# Quad-Load-Cell-Amplifier-to-RS-485-Conv-.net
KiCad netlist of a schematic drawn in EAGLE
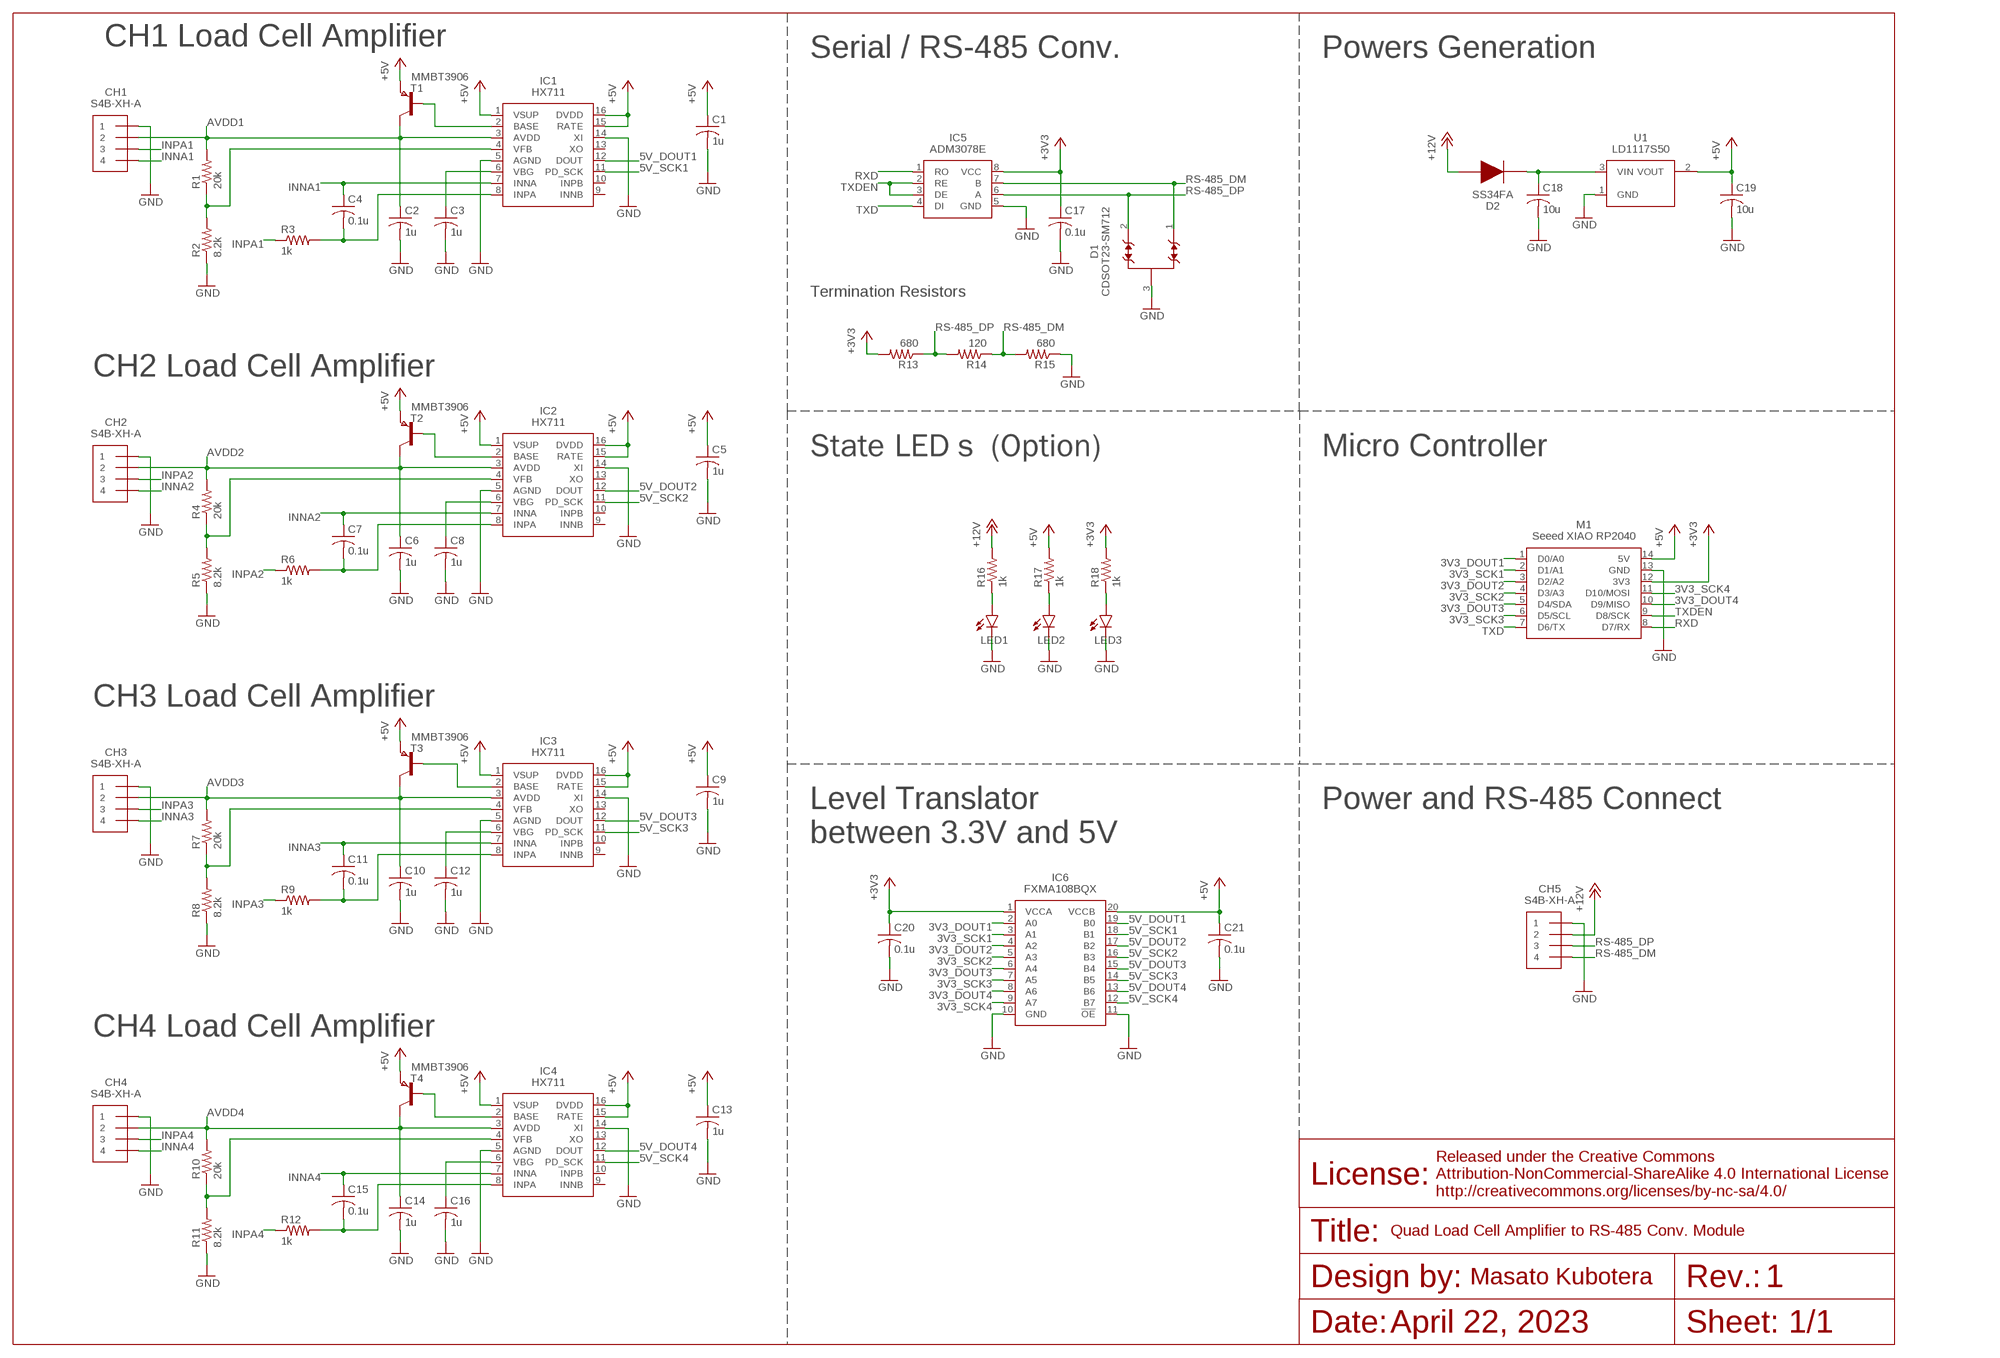
[diagram p0: schematic, sheet 1]

(export (version "E")
  (design (tool "Eeschema 10.0.6"))
  (components
    (comp (ref "C1")
      (value "1u")
      (footprint "eagle-import:C0603")
      (libsource (lib "eagle-import") (part "C-USC0603"))
    )
    (comp (ref "C2")
      (value "1u")
      (footprint "eagle-import:C0603")
      (libsource (lib "eagle-import") (part "C-USC0603"))
    )
    (comp (ref "C3")
      (value "1u")
      (footprint "eagle-import:C0603")
      (libsource (lib "eagle-import") (part "C-USC0603"))
    )
    (comp (ref "C4")
      (value "0.1u")
      (footprint "eagle-import:C0603")
      (libsource (lib "eagle-import") (part "C-USC0603"))
    )
    (comp (ref "C5")
      (value "1u")
      (footprint "eagle-import:C0603")
      (libsource (lib "eagle-import") (part "C-USC0603"))
    )
    (comp (ref "C6")
      (value "1u")
      (footprint "eagle-import:C0603")
      (libsource (lib "eagle-import") (part "C-USC0603"))
    )
    (comp (ref "C7")
      (value "0.1u")
      (footprint "eagle-import:C0603")
      (libsource (lib "eagle-import") (part "C-USC0603"))
    )
    (comp (ref "C8")
      (value "1u")
      (footprint "eagle-import:C0603")
      (libsource (lib "eagle-import") (part "C-USC0603"))
    )
    (comp (ref "C9")
      (value "1u")
      (footprint "eagle-import:C0603")
      (libsource (lib "eagle-import") (part "C-USC0603"))
    )
    (comp (ref "C10")
      (value "1u")
      (footprint "eagle-import:C0603")
      (libsource (lib "eagle-import") (part "C-USC0603"))
    )
    (comp (ref "C11")
      (value "0.1u")
      (footprint "eagle-import:C0603")
      (libsource (lib "eagle-import") (part "C-USC0603"))
    )
    (comp (ref "C12")
      (value "1u")
      (footprint "eagle-import:C0603")
      (libsource (lib "eagle-import") (part "C-USC0603"))
    )
    (comp (ref "C13")
      (value "1u")
      (footprint "eagle-import:C0603")
      (libsource (lib "eagle-import") (part "C-USC0603"))
    )
    (comp (ref "C14")
      (value "1u")
      (footprint "eagle-import:C0603")
      (libsource (lib "eagle-import") (part "C-USC0603"))
    )
    (comp (ref "C15")
      (value "0.1u")
      (footprint "eagle-import:C0603")
      (libsource (lib "eagle-import") (part "C-USC0603"))
    )
    (comp (ref "C16")
      (value "1u")
      (footprint "eagle-import:C0603")
      (libsource (lib "eagle-import") (part "C-USC0603"))
    )
    (comp (ref "C17")
      (value "0.1u")
      (footprint "eagle-import:C0603")
      (libsource (lib "eagle-import") (part "C-USC0603"))
    )
    (comp (ref "C18")
      (value "10u")
      (footprint "eagle-import:C0603")
      (libsource (lib "eagle-import") (part "C-USC0603"))
    )
    (comp (ref "C19")
      (value "10u")
      (footprint "eagle-import:C0603")
      (libsource (lib "eagle-import") (part "C-USC0603"))
    )
    (comp (ref "C20")
      (value "0.1u")
      (footprint "eagle-import:C0603")
      (libsource (lib "eagle-import") (part "C-USC0603"))
    )
    (comp (ref "C21")
      (value "0.1u")
      (footprint "eagle-import:C0603")
      (libsource (lib "eagle-import") (part "C-USC0603"))
    )
    (comp (ref "CH1")
      (value "S4B-XH-A")
      (footprint "eagle-import:S4B-XH-A")
      (libsource (lib "eagle-import") (part "S4B-XH-A"))
    )
    (comp (ref "CH2")
      (value "S4B-XH-A")
      (footprint "eagle-import:S4B-XH-A")
      (libsource (lib "eagle-import") (part "S4B-XH-A"))
    )
    (comp (ref "CH3")
      (value "S4B-XH-A")
      (footprint "eagle-import:S4B-XH-A")
      (libsource (lib "eagle-import") (part "S4B-XH-A"))
    )
    (comp (ref "CH4")
      (value "S4B-XH-A")
      (footprint "eagle-import:S4B-XH-A")
      (libsource (lib "eagle-import") (part "S4B-XH-A"))
    )
    (comp (ref "CH5")
      (value "S4B-XH-A")
      (footprint "eagle-import:S4B-XH-A")
      (libsource (lib "eagle-import") (part "S4B-XH-A"))
    )
    (comp (ref "D1")
      (value "CDSOT23-SM712")
      (footprint "eagle-import:SOT-23-3")
      (libsource (lib "eagle-import") (part "CDSOT23-SM712"))
    )
    (comp (ref "D2")
      (value "SS34FA")
      (footprint "eagle-import:SS34FA")
      (libsource (lib "eagle-import") (part "SS34FA"))
    )
    (comp (ref "IC1")
      (value "HX711")
      (footprint "eagle-import:HX711")
      (libsource (lib "eagle-import") (part "HX711"))
    )
    (comp (ref "IC2")
      (value "HX711")
      (footprint "eagle-import:HX711")
      (libsource (lib "eagle-import") (part "HX711"))
    )
    (comp (ref "IC3")
      (value "HX711")
      (footprint "eagle-import:HX711")
      (libsource (lib "eagle-import") (part "HX711"))
    )
    (comp (ref "IC4")
      (value "HX711")
      (footprint "eagle-import:HX711")
      (libsource (lib "eagle-import") (part "HX711"))
    )
    (comp (ref "IC5")
      (value "ADM3078E")
      (footprint "eagle-import:ADM3078E")
      (libsource (lib "eagle-import") (part "ADM3078E"))
    )
    (comp (ref "IC6")
      (value "FXMA108BQX")
      (footprint "eagle-import:QFN-20")
      (libsource (lib "eagle-import") (part "FXMA108BQX"))
    )
    (comp (ref "LED1")
      (value "LEDSML0603")
      (footprint "eagle-import:SML0603")
      (libsource (lib "eagle-import") (part "LEDSML0603"))
    )
    (comp (ref "LED2")
      (value "LEDSML0603")
      (footprint "eagle-import:SML0603")
      (libsource (lib "eagle-import") (part "LEDSML0603"))
    )
    (comp (ref "LED3")
      (value "LEDSML0603")
      (footprint "eagle-import:SML0603")
      (libsource (lib "eagle-import") (part "LEDSML0603"))
    )
    (comp (ref "M1")
      (value "SEEED_XIAO_RP2040_HOLE")
      (footprint "eagle-import:SEEED_XIAO_HOLE")
      (libsource (lib "eagle-import") (part "SEEED_XIAO_RP2040_HOLE"))
    )
    (comp (ref "R1")
      (value "20k")
      (footprint "eagle-import:R0603")
      (libsource (lib "eagle-import") (part "R-US_R0603"))
    )
    (comp (ref "R2")
      (value "8.2k")
      (footprint "eagle-import:R0603")
      (libsource (lib "eagle-import") (part "R-US_R0603"))
    )
    (comp (ref "R3")
      (value "1k")
      (footprint "eagle-import:R0603")
      (libsource (lib "eagle-import") (part "R-US_R0603"))
    )
    (comp (ref "R4")
      (value "20k")
      (footprint "eagle-import:R0603")
      (libsource (lib "eagle-import") (part "R-US_R0603"))
    )
    (comp (ref "R5")
      (value "8.2k")
      (footprint "eagle-import:R0603")
      (libsource (lib "eagle-import") (part "R-US_R0603"))
    )
    (comp (ref "R6")
      (value "1k")
      (footprint "eagle-import:R0603")
      (libsource (lib "eagle-import") (part "R-US_R0603"))
    )
    (comp (ref "R7")
      (value "20k")
      (footprint "eagle-import:R0603")
      (libsource (lib "eagle-import") (part "R-US_R0603"))
    )
    (comp (ref "R8")
      (value "8.2k")
      (footprint "eagle-import:R0603")
      (libsource (lib "eagle-import") (part "R-US_R0603"))
    )
    (comp (ref "R9")
      (value "1k")
      (footprint "eagle-import:R0603")
      (libsource (lib "eagle-import") (part "R-US_R0603"))
    )
    (comp (ref "R10")
      (value "20k")
      (footprint "eagle-import:R0603")
      (libsource (lib "eagle-import") (part "R-US_R0603"))
    )
    (comp (ref "R11")
      (value "8.2k")
      (footprint "eagle-import:R0603")
      (libsource (lib "eagle-import") (part "R-US_R0603"))
    )
    (comp (ref "R12")
      (value "1k")
      (footprint "eagle-import:R0603")
      (libsource (lib "eagle-import") (part "R-US_R0603"))
    )
    (comp (ref "R13")
      (value "680")
      (footprint "eagle-import:R0603")
      (libsource (lib "eagle-import") (part "R-US_R0603"))
    )
    (comp (ref "R14")
      (value "120")
      (footprint "eagle-import:R0603")
      (libsource (lib "eagle-import") (part "R-US_R0603"))
    )
    (comp (ref "R15")
      (value "680")
      (footprint "eagle-import:R0603")
      (libsource (lib "eagle-import") (part "R-US_R0603"))
    )
    (comp (ref "R16")
      (value "1k")
      (footprint "eagle-import:R0603")
      (libsource (lib "eagle-import") (part "R-US_R0603"))
    )
    (comp (ref "R17")
      (value "1k")
      (footprint "eagle-import:R0603")
      (libsource (lib "eagle-import") (part "R-US_R0603"))
    )
    (comp (ref "R18")
      (value "1k")
      (footprint "eagle-import:R0603")
      (libsource (lib "eagle-import") (part "R-US_R0603"))
    )
    (comp (ref "T1")
      (value "MMBT3906")
      (footprint "eagle-import:SOT-23")
      (fields (field (name "MPN") "DSS20200L-7"))
      (libsource (lib "eagle-import") (part "PNPSOT23"))
    )
    (comp (ref "T2")
      (value "MMBT3906")
      (footprint "eagle-import:SOT-23")
      (fields (field (name "MPN") "DSS20200L-7"))
      (libsource (lib "eagle-import") (part "PNPSOT23"))
    )
    (comp (ref "T3")
      (value "MMBT3906")
      (footprint "eagle-import:SOT-23")
      (fields (field (name "MPN") "DSS20200L-7"))
      (libsource (lib "eagle-import") (part "PNPSOT23"))
    )
    (comp (ref "T4")
      (value "MMBT3906")
      (footprint "eagle-import:SOT-23")
      (fields (field (name "MPN") "DSS20200L-7"))
      (libsource (lib "eagle-import") (part "PNPSOT23"))
    )
    (comp (ref "U1")
      (value "LD1117S50")
      (footprint "eagle-import:SOT-223")
      (libsource (lib "eagle-import") (part "LD1117S50"))
    )
  )
  (nets
    (net (code "1") (name "+3V3") (class "Default")
      (node (ref "C17") (pin "1") (pinfunction "1_1") (pintype "passive"))
      (node (ref "C20") (pin "1") (pinfunction "1_1") (pintype "passive"))
      (node (ref "IC5") (pin "8") (pinfunction "VCC_8") (pintype "bidirectional"))
      (node (ref "IC6") (pin "1") (pinfunction "VCCA_1") (pintype "bidirectional"))
      (node (ref "M1") (pin "12") (pinfunction "3V3_12") (pintype "bidirectional"))
      (node (ref "R13") (pin "2") (pinfunction "2_2") (pintype "passive"))
      (node (ref "R18") (pin "2") (pinfunction "2_2") (pintype "passive"))
    )
    (net (code "2") (name "+5V") (class "Default")
      (node (ref "C1") (pin "1") (pinfunction "1_1") (pintype "passive"))
      (node (ref "C13") (pin "1") (pinfunction "1_1") (pintype "passive"))
      (node (ref "C19") (pin "1") (pinfunction "1_1") (pintype "passive"))
      (node (ref "C21") (pin "1") (pinfunction "1_1") (pintype "passive"))
      (node (ref "C5") (pin "1") (pinfunction "1_1") (pintype "passive"))
      (node (ref "C9") (pin "1") (pinfunction "1_1") (pintype "passive"))
      (node (ref "IC1") (pin "1") (pinfunction "VSUP_1") (pintype "bidirectional"))
      (node (ref "IC1") (pin "15") (pinfunction "RATE_15") (pintype "bidirectional"))
      (node (ref "IC1") (pin "16") (pinfunction "DVDD_16") (pintype "bidirectional"))
      (node (ref "IC2") (pin "1") (pinfunction "VSUP_1") (pintype "bidirectional"))
      (node (ref "IC2") (pin "15") (pinfunction "RATE_15") (pintype "bidirectional"))
      (node (ref "IC2") (pin "16") (pinfunction "DVDD_16") (pintype "bidirectional"))
      (node (ref "IC3") (pin "1") (pinfunction "VSUP_1") (pintype "bidirectional"))
      (node (ref "IC3") (pin "15") (pinfunction "RATE_15") (pintype "bidirectional"))
      (node (ref "IC3") (pin "16") (pinfunction "DVDD_16") (pintype "bidirectional"))
      (node (ref "IC4") (pin "1") (pinfunction "VSUP_1") (pintype "bidirectional"))
      (node (ref "IC4") (pin "15") (pinfunction "RATE_15") (pintype "bidirectional"))
      (node (ref "IC4") (pin "16") (pinfunction "DVDD_16") (pintype "bidirectional"))
      (node (ref "IC6") (pin "20") (pinfunction "VCCB_20") (pintype "bidirectional"))
      (node (ref "M1") (pin "14") (pinfunction "5V_14") (pintype "bidirectional"))
      (node (ref "R17") (pin "2") (pinfunction "2_2") (pintype "passive"))
      (node (ref "T1") (pin "2") (pinfunction "E_2") (pintype "passive"))
      (node (ref "T2") (pin "2") (pinfunction "E_2") (pintype "passive"))
      (node (ref "T3") (pin "2") (pinfunction "E_2") (pintype "passive"))
      (node (ref "T4") (pin "2") (pinfunction "E_2") (pintype "passive"))
      (node (ref "U1") (pin "2") (pinfunction "VOUT_2") (pintype "bidirectional"))
    )
    (net (code "3") (name "+12V") (class "Default")
      (node (ref "CH5") (pin "2") (pinfunction "2_2") (pintype "bidirectional"))
      (node (ref "D2") (pin "2") (pinfunction "2_2") (pintype "bidirectional"))
      (node (ref "R16") (pin "2") (pinfunction "2_2") (pintype "passive"))
    )
    (net (code "4") (name "/3V3_DOUT1") (class "Default")
      (node (ref "IC6") (pin "2") (pinfunction "A0_2") (pintype "bidirectional"))
      (node (ref "M1") (pin "1") (pinfunction "D0/A0_1") (pintype "bidirectional"))
    )
    (net (code "5") (name "/3V3_DOUT2") (class "Default")
      (node (ref "IC6") (pin "4") (pinfunction "A2_4") (pintype "bidirectional"))
      (node (ref "M1") (pin "3") (pinfunction "D2/A2_3") (pintype "bidirectional"))
    )
    (net (code "6") (name "/3V3_DOUT3") (class "Default")
      (node (ref "IC6") (pin "6") (pinfunction "A4_6") (pintype "bidirectional"))
      (node (ref "M1") (pin "5") (pinfunction "D4/SDA_5") (pintype "bidirectional"))
    )
    (net (code "7") (name "/3V3_DOUT4") (class "Default")
      (node (ref "IC6") (pin "8") (pinfunction "A6_8") (pintype "bidirectional"))
      (node (ref "M1") (pin "10") (pinfunction "D9/MISO_10") (pintype "bidirectional"))
    )
    (net (code "8") (name "/3V3_SCK1") (class "Default")
      (node (ref "IC6") (pin "3") (pinfunction "A1_3") (pintype "bidirectional"))
      (node (ref "M1") (pin "2") (pinfunction "D1/A1_2") (pintype "bidirectional"))
    )
    (net (code "9") (name "/3V3_SCK2") (class "Default")
      (node (ref "IC6") (pin "5") (pinfunction "A3_5") (pintype "bidirectional"))
      (node (ref "M1") (pin "4") (pinfunction "D3/A3_4") (pintype "bidirectional"))
    )
    (net (code "10") (name "/3V3_SCK3") (class "Default")
      (node (ref "IC6") (pin "7") (pinfunction "A5_7") (pintype "bidirectional"))
      (node (ref "M1") (pin "6") (pinfunction "D5/SCL_6") (pintype "bidirectional"))
    )
    (net (code "11") (name "/3V3_SCK4") (class "Default")
      (node (ref "IC6") (pin "9") (pinfunction "A7_9") (pintype "bidirectional"))
      (node (ref "M1") (pin "11") (pinfunction "D10/MOSI_11") (pintype "bidirectional"))
    )
    (net (code "12") (name "/5V_DOUT1") (class "Default")
      (node (ref "IC1") (pin "12") (pinfunction "DOUT_12") (pintype "bidirectional"))
      (node (ref "IC6") (pin "19") (pinfunction "B0_19") (pintype "bidirectional"))
    )
    (net (code "13") (name "/5V_DOUT2") (class "Default")
      (node (ref "IC2") (pin "12") (pinfunction "DOUT_12") (pintype "bidirectional"))
      (node (ref "IC6") (pin "17") (pinfunction "B2_17") (pintype "bidirectional"))
    )
    (net (code "14") (name "/5V_DOUT3") (class "Default")
      (node (ref "IC3") (pin "12") (pinfunction "DOUT_12") (pintype "bidirectional"))
      (node (ref "IC6") (pin "15") (pinfunction "B4_15") (pintype "bidirectional"))
    )
    (net (code "15") (name "/5V_DOUT4") (class "Default")
      (node (ref "IC4") (pin "12") (pinfunction "DOUT_12") (pintype "bidirectional"))
      (node (ref "IC6") (pin "13") (pinfunction "B6_13") (pintype "bidirectional"))
    )
    (net (code "16") (name "/5V_SCK1") (class "Default")
      (node (ref "IC1") (pin "11") (pinfunction "PD_SCK_11") (pintype "bidirectional"))
      (node (ref "IC6") (pin "18") (pinfunction "B1_18") (pintype "bidirectional"))
    )
    (net (code "17") (name "/5V_SCK2") (class "Default")
      (node (ref "IC2") (pin "11") (pinfunction "PD_SCK_11") (pintype "bidirectional"))
      (node (ref "IC6") (pin "16") (pinfunction "B3_16") (pintype "bidirectional"))
    )
    (net (code "18") (name "/5V_SCK3") (class "Default")
      (node (ref "IC3") (pin "11") (pinfunction "PD_SCK_11") (pintype "bidirectional"))
      (node (ref "IC6") (pin "14") (pinfunction "B5_14") (pintype "bidirectional"))
    )
    (net (code "19") (name "/5V_SCK4") (class "Default")
      (node (ref "IC4") (pin "11") (pinfunction "PD_SCK_11") (pintype "bidirectional"))
      (node (ref "IC6") (pin "12") (pinfunction "B7_12") (pintype "bidirectional"))
    )
    (net (code "20") (name "/AVDD1") (class "Default")
      (node (ref "C2") (pin "1") (pinfunction "1_1") (pintype "passive"))
      (node (ref "CH1") (pin "2") (pinfunction "2_2") (pintype "bidirectional"))
      (node (ref "IC1") (pin "3") (pinfunction "AVDD_3") (pintype "bidirectional"))
      (node (ref "R1") (pin "2") (pinfunction "2_2") (pintype "passive"))
      (node (ref "T1") (pin "1") (pinfunction "C_1") (pintype "passive"))
    )
    (net (code "21") (name "/AVDD2") (class "Default")
      (node (ref "C6") (pin "1") (pinfunction "1_1") (pintype "passive"))
      (node (ref "CH2") (pin "2") (pinfunction "2_2") (pintype "bidirectional"))
      (node (ref "IC2") (pin "3") (pinfunction "AVDD_3") (pintype "bidirectional"))
      (node (ref "R4") (pin "2") (pinfunction "2_2") (pintype "passive"))
      (node (ref "T2") (pin "1") (pinfunction "C_1") (pintype "passive"))
    )
    (net (code "22") (name "/AVDD3") (class "Default")
      (node (ref "C10") (pin "1") (pinfunction "1_1") (pintype "passive"))
      (node (ref "CH3") (pin "2") (pinfunction "2_2") (pintype "bidirectional"))
      (node (ref "IC3") (pin "3") (pinfunction "AVDD_3") (pintype "bidirectional"))
      (node (ref "R7") (pin "2") (pinfunction "2_2") (pintype "passive"))
      (node (ref "T3") (pin "1") (pinfunction "C_1") (pintype "passive"))
    )
    (net (code "23") (name "/AVDD4") (class "Default")
      (node (ref "C14") (pin "1") (pinfunction "1_1") (pintype "passive"))
      (node (ref "CH4") (pin "2") (pinfunction "2_2") (pintype "bidirectional"))
      (node (ref "IC4") (pin "3") (pinfunction "AVDD_3") (pintype "bidirectional"))
      (node (ref "R10") (pin "2") (pinfunction "2_2") (pintype "passive"))
      (node (ref "T4") (pin "1") (pinfunction "C_1") (pintype "passive"))
    )
    (net (code "24") (name "/INNA1") (class "Default")
      (node (ref "C4") (pin "1") (pinfunction "1_1") (pintype "passive"))
      (node (ref "CH1") (pin "4") (pinfunction "4_4") (pintype "bidirectional"))
      (node (ref "IC1") (pin "7") (pinfunction "INNA_7") (pintype "bidirectional"))
    )
    (net (code "25") (name "/INNA2") (class "Default")
      (node (ref "C7") (pin "1") (pinfunction "1_1") (pintype "passive"))
      (node (ref "CH2") (pin "4") (pinfunction "4_4") (pintype "bidirectional"))
      (node (ref "IC2") (pin "7") (pinfunction "INNA_7") (pintype "bidirectional"))
    )
    (net (code "26") (name "/INNA3") (class "Default")
      (node (ref "C11") (pin "1") (pinfunction "1_1") (pintype "passive"))
      (node (ref "CH3") (pin "4") (pinfunction "4_4") (pintype "bidirectional"))
      (node (ref "IC3") (pin "7") (pinfunction "INNA_7") (pintype "bidirectional"))
    )
    (net (code "27") (name "/INNA4") (class "Default")
      (node (ref "C15") (pin "1") (pinfunction "1_1") (pintype "passive"))
      (node (ref "CH4") (pin "4") (pinfunction "4_4") (pintype "bidirectional"))
      (node (ref "IC4") (pin "7") (pinfunction "INNA_7") (pintype "bidirectional"))
    )
    (net (code "28") (name "/INPA1") (class "Default")
      (node (ref "CH1") (pin "3") (pinfunction "3_3") (pintype "bidirectional"))
      (node (ref "R3") (pin "1") (pinfunction "1_1") (pintype "passive"))
    )
    (net (code "29") (name "/INPA2") (class "Default")
      (node (ref "CH2") (pin "3") (pinfunction "3_3") (pintype "bidirectional"))
      (node (ref "R6") (pin "1") (pinfunction "1_1") (pintype "passive"))
    )
    (net (code "30") (name "/INPA3") (class "Default")
      (node (ref "CH3") (pin "3") (pinfunction "3_3") (pintype "bidirectional"))
      (node (ref "R9") (pin "1") (pinfunction "1_1") (pintype "passive"))
    )
    (net (code "31") (name "/INPA4") (class "Default")
      (node (ref "CH4") (pin "3") (pinfunction "3_3") (pintype "bidirectional"))
      (node (ref "R12") (pin "1") (pinfunction "1_1") (pintype "passive"))
    )
    (net (code "32") (name "/RS-485_DM") (class "Default")
      (node (ref "CH5") (pin "4") (pinfunction "4_4") (pintype "bidirectional"))
      (node (ref "D1") (pin "1") (pinfunction "1_1") (pintype "bidirectional"))
      (node (ref "IC5") (pin "7") (pinfunction "B_7") (pintype "bidirectional"))
      (node (ref "R14") (pin "1") (pinfunction "1_1") (pintype "passive"))
      (node (ref "R15") (pin "2") (pinfunction "2_2") (pintype "passive"))
    )
    (net (code "33") (name "/RS-485_DP") (class "Default")
      (node (ref "CH5") (pin "3") (pinfunction "3_3") (pintype "bidirectional"))
      (node (ref "D1") (pin "2") (pinfunction "2_2") (pintype "bidirectional"))
      (node (ref "IC5") (pin "6") (pinfunction "A_6") (pintype "bidirectional"))
      (node (ref "R13") (pin "1") (pinfunction "1_1") (pintype "passive"))
      (node (ref "R14") (pin "2") (pinfunction "2_2") (pintype "passive"))
    )
    (net (code "34") (name "/RXD") (class "Default")
      (node (ref "IC5") (pin "1") (pinfunction "RO_1") (pintype "bidirectional"))
      (node (ref "M1") (pin "8") (pinfunction "D7/RX_8") (pintype "bidirectional"))
    )
    (net (code "35") (name "/TXD") (class "Default")
      (node (ref "IC5") (pin "4") (pinfunction "DI_4") (pintype "bidirectional"))
      (node (ref "M1") (pin "7") (pinfunction "D6/TX_7") (pintype "bidirectional"))
    )
    (net (code "36") (name "/TXDEN") (class "Default")
      (node (ref "IC5") (pin "2") (pinfunction "RE_2") (pintype "bidirectional"))
      (node (ref "IC5") (pin "3") (pinfunction "DE_3") (pintype "bidirectional"))
      (node (ref "M1") (pin "9") (pinfunction "D8/SCK_9") (pintype "bidirectional"))
    )
    (net (code "37") (name "GND") (class "Default")
      (node (ref "C1") (pin "2") (pinfunction "2_2") (pintype "passive"))
      (node (ref "C10") (pin "2") (pinfunction "2_2") (pintype "passive"))
      (node (ref "C12") (pin "2") (pinfunction "2_2") (pintype "passive"))
      (node (ref "C13") (pin "2") (pinfunction "2_2") (pintype "passive"))
      (node (ref "C14") (pin "2") (pinfunction "2_2") (pintype "passive"))
      (node (ref "C16") (pin "2") (pinfunction "2_2") (pintype "passive"))
      (node (ref "C17") (pin "2") (pinfunction "2_2") (pintype "passive"))
      (node (ref "C18") (pin "2") (pinfunction "2_2") (pintype "passive"))
      (node (ref "C19") (pin "2") (pinfunction "2_2") (pintype "passive"))
      (node (ref "C2") (pin "2") (pinfunction "2_2") (pintype "passive"))
      (node (ref "C20") (pin "2") (pinfunction "2_2") (pintype "passive"))
      (node (ref "C21") (pin "2") (pinfunction "2_2") (pintype "passive"))
      (node (ref "C3") (pin "2") (pinfunction "2_2") (pintype "passive"))
      (node (ref "C5") (pin "2") (pinfunction "2_2") (pintype "passive"))
      (node (ref "C6") (pin "2") (pinfunction "2_2") (pintype "passive"))
      (node (ref "C8") (pin "2") (pinfunction "2_2") (pintype "passive"))
      (node (ref "C9") (pin "2") (pinfunction "2_2") (pintype "passive"))
      (node (ref "CH1") (pin "1") (pinfunction "1_1") (pintype "bidirectional"))
      (node (ref "CH2") (pin "1") (pinfunction "1_1") (pintype "bidirectional"))
      (node (ref "CH3") (pin "1") (pinfunction "1_1") (pintype "bidirectional"))
      (node (ref "CH4") (pin "1") (pinfunction "1_1") (pintype "bidirectional"))
      (node (ref "CH5") (pin "1") (pinfunction "1_1") (pintype "bidirectional"))
      (node (ref "D1") (pin "3") (pinfunction "3_3") (pintype "bidirectional"))
      (node (ref "IC1") (pin "14") (pinfunction "XI_14") (pintype "bidirectional"))
      (node (ref "IC1") (pin "5") (pinfunction "AGND_5") (pintype "bidirectional"))
      (node (ref "IC2") (pin "14") (pinfunction "XI_14") (pintype "bidirectional"))
      (node (ref "IC2") (pin "5") (pinfunction "AGND_5") (pintype "bidirectional"))
      (node (ref "IC3") (pin "14") (pinfunction "XI_14") (pintype "bidirectional"))
      (node (ref "IC3") (pin "5") (pinfunction "AGND_5") (pintype "bidirectional"))
      (node (ref "IC4") (pin "14") (pinfunction "XI_14") (pintype "bidirectional"))
      (node (ref "IC4") (pin "5") (pinfunction "AGND_5") (pintype "bidirectional"))
      (node (ref "IC5") (pin "5") (pinfunction "GND_5") (pintype "bidirectional"))
      (node (ref "IC6") (pin "10") (pinfunction "GND_10") (pintype "bidirectional"))
      (node (ref "IC6") (pin "11") (pinfunction "~{OE}_11") (pintype "bidirectional"))
      (node (ref "LED1") (pin "C") (pinfunction "C_C") (pintype "passive"))
      (node (ref "LED2") (pin "C") (pinfunction "C_C") (pintype "passive"))
      (node (ref "LED3") (pin "C") (pinfunction "C_C") (pintype "passive"))
      (node (ref "M1") (pin "13") (pinfunction "GND_13") (pintype "bidirectional"))
      (node (ref "R11") (pin "1") (pinfunction "1_1") (pintype "passive"))
      (node (ref "R15") (pin "1") (pinfunction "1_1") (pintype "passive"))
      (node (ref "R2") (pin "1") (pinfunction "1_1") (pintype "passive"))
      (node (ref "R5") (pin "1") (pinfunction "1_1") (pintype "passive"))
      (node (ref "R8") (pin "1") (pinfunction "1_1") (pintype "passive"))
      (node (ref "U1") (pin "1") (pinfunction "GND_1") (pintype "bidirectional"))
    )
    (net (code "38") (name "Net-(IC1-BASE)") (class "Default")
      (node (ref "IC1") (pin "2") (pinfunction "BASE_2") (pintype "bidirectional"))
      (node (ref "T1") (pin "3") (pinfunction "B_3") (pintype "passive"))
    )
    (net (code "39") (name "Net-(IC1-INPA)") (class "Default")
      (node (ref "C4") (pin "2") (pinfunction "2_2") (pintype "passive"))
      (node (ref "IC1") (pin "8") (pinfunction "INPA_8") (pintype "bidirectional"))
      (node (ref "R3") (pin "2") (pinfunction "2_2") (pintype "passive"))
    )
    (net (code "40") (name "Net-(IC1-VBG)") (class "Default")
      (node (ref "C3") (pin "1") (pinfunction "1_1") (pintype "passive"))
      (node (ref "IC1") (pin "6") (pinfunction "VBG_6") (pintype "bidirectional"))
    )
    (net (code "41") (name "Net-(IC1-VFB)") (class "Default")
      (node (ref "IC1") (pin "4") (pinfunction "VFB_4") (pintype "bidirectional"))
      (node (ref "R1") (pin "1") (pinfunction "1_1") (pintype "passive"))
      (node (ref "R2") (pin "2") (pinfunction "2_2") (pintype "passive"))
    )
    (net (code "42") (name "Net-(IC2-BASE)") (class "Default")
      (node (ref "IC2") (pin "2") (pinfunction "BASE_2") (pintype "bidirectional"))
      (node (ref "T2") (pin "3") (pinfunction "B_3") (pintype "passive"))
    )
    (net (code "43") (name "Net-(IC2-INPA)") (class "Default")
      (node (ref "C7") (pin "2") (pinfunction "2_2") (pintype "passive"))
      (node (ref "IC2") (pin "8") (pinfunction "INPA_8") (pintype "bidirectional"))
      (node (ref "R6") (pin "2") (pinfunction "2_2") (pintype "passive"))
    )
    (net (code "44") (name "Net-(IC2-VBG)") (class "Default")
      (node (ref "C8") (pin "1") (pinfunction "1_1") (pintype "passive"))
      (node (ref "IC2") (pin "6") (pinfunction "VBG_6") (pintype "bidirectional"))
    )
    (net (code "45") (name "Net-(IC2-VFB)") (class "Default")
      (node (ref "IC2") (pin "4") (pinfunction "VFB_4") (pintype "bidirectional"))
      (node (ref "R4") (pin "1") (pinfunction "1_1") (pintype "passive"))
      (node (ref "R5") (pin "2") (pinfunction "2_2") (pintype "passive"))
    )
    (net (code "46") (name "Net-(IC3-BASE)") (class "Default")
      (node (ref "IC3") (pin "2") (pinfunction "BASE_2") (pintype "bidirectional"))
      (node (ref "T3") (pin "3") (pinfunction "B_3") (pintype "passive"))
    )
    (net (code "47") (name "Net-(IC3-INPA)") (class "Default")
      (node (ref "C11") (pin "2") (pinfunction "2_2") (pintype "passive"))
      (node (ref "IC3") (pin "8") (pinfunction "INPA_8") (pintype "bidirectional"))
      (node (ref "R9") (pin "2") (pinfunction "2_2") (pintype "passive"))
    )
    (net (code "48") (name "Net-(IC3-VBG)") (class "Default")
      (node (ref "C12") (pin "1") (pinfunction "1_1") (pintype "passive"))
      (node (ref "IC3") (pin "6") (pinfunction "VBG_6") (pintype "bidirectional"))
    )
    (net (code "49") (name "Net-(IC3-VFB)") (class "Default")
      (node (ref "IC3") (pin "4") (pinfunction "VFB_4") (pintype "bidirectional"))
      (node (ref "R7") (pin "1") (pinfunction "1_1") (pintype "passive"))
      (node (ref "R8") (pin "2") (pinfunction "2_2") (pintype "passive"))
    )
    (net (code "50") (name "Net-(IC4-BASE)") (class "Default")
      (node (ref "IC4") (pin "2") (pinfunction "BASE_2") (pintype "bidirectional"))
      (node (ref "T4") (pin "3") (pinfunction "B_3") (pintype "passive"))
    )
    (net (code "51") (name "Net-(IC4-INPA)") (class "Default")
      (node (ref "C15") (pin "2") (pinfunction "2_2") (pintype "passive"))
      (node (ref "IC4") (pin "8") (pinfunction "INPA_8") (pintype "bidirectional"))
      (node (ref "R12") (pin "2") (pinfunction "2_2") (pintype "passive"))
    )
    (net (code "52") (name "Net-(IC4-VBG)") (class "Default")
      (node (ref "C16") (pin "1") (pinfunction "1_1") (pintype "passive"))
      (node (ref "IC4") (pin "6") (pinfunction "VBG_6") (pintype "bidirectional"))
    )
    (net (code "53") (name "Net-(IC4-VFB)") (class "Default")
      (node (ref "IC4") (pin "4") (pinfunction "VFB_4") (pintype "bidirectional"))
      (node (ref "R10") (pin "1") (pinfunction "1_1") (pintype "passive"))
      (node (ref "R11") (pin "2") (pinfunction "2_2") (pintype "passive"))
    )
    (net (code "54") (name "Net-(LED1-PadA)") (class "Default")
      (node (ref "LED1") (pin "A") (pinfunction "A_A") (pintype "passive"))
      (node (ref "R16") (pin "1") (pinfunction "1_1") (pintype "passive"))
    )
    (net (code "55") (name "Net-(LED2-PadA)") (class "Default")
      (node (ref "LED2") (pin "A") (pinfunction "A_A") (pintype "passive"))
      (node (ref "R17") (pin "1") (pinfunction "1_1") (pintype "passive"))
    )
    (net (code "56") (name "Net-(LED3-PadA)") (class "Default")
      (node (ref "LED3") (pin "A") (pinfunction "A_A") (pintype "passive"))
      (node (ref "R18") (pin "1") (pinfunction "1_1") (pintype "passive"))
    )
    (net (code "57") (name "Net-(U1-VIN)") (class "Default")
      (node (ref "C18") (pin "1") (pinfunction "1_1") (pintype "passive"))
      (node (ref "D2") (pin "1") (pinfunction "1_1") (pintype "bidirectional"))
      (node (ref "U1") (pin "3") (pinfunction "VIN_3") (pintype "bidirectional"))
    )
    (net (code "58") (name "unconnected-(IC1-INNB-Pad9)") (class "Default")
      (node (ref "IC1") (pin "9") (pinfunction "INNB_9") (pintype "bidirectional"))
    )
    (net (code "59") (name "unconnected-(IC1-INPB-Pad10)") (class "Default")
      (node (ref "IC1") (pin "10") (pinfunction "INPB_10") (pintype "bidirectional"))
    )
    (net (code "60") (name "unconnected-(IC1-XO-Pad13)") (class "Default")
      (node (ref "IC1") (pin "13") (pinfunction "XO_13") (pintype "bidirectional"))
    )
    (net (code "61") (name "unconnected-(IC2-INNB-Pad9)") (class "Default")
      (node (ref "IC2") (pin "9") (pinfunction "INNB_9") (pintype "bidirectional"))
    )
    (net (code "62") (name "unconnected-(IC2-INPB-Pad10)") (class "Default")
      (node (ref "IC2") (pin "10") (pinfunction "INPB_10") (pintype "bidirectional"))
    )
    (net (code "63") (name "unconnected-(IC2-XO-Pad13)") (class "Default")
      (node (ref "IC2") (pin "13") (pinfunction "XO_13") (pintype "bidirectional"))
    )
    (net (code "64") (name "unconnected-(IC3-INNB-Pad9)") (class "Default")
      (node (ref "IC3") (pin "9") (pinfunction "INNB_9") (pintype "bidirectional"))
    )
    (net (code "65") (name "unconnected-(IC3-INPB-Pad10)") (class "Default")
      (node (ref "IC3") (pin "10") (pinfunction "INPB_10") (pintype "bidirectional"))
    )
    (net (code "66") (name "unconnected-(IC3-XO-Pad13)") (class "Default")
      (node (ref "IC3") (pin "13") (pinfunction "XO_13") (pintype "bidirectional"))
    )
    (net (code "67") (name "unconnected-(IC4-INNB-Pad9)") (class "Default")
      (node (ref "IC4") (pin "9") (pinfunction "INNB_9") (pintype "bidirectional"))
    )
    (net (code "68") (name "unconnected-(IC4-INPB-Pad10)") (class "Default")
      (node (ref "IC4") (pin "10") (pinfunction "INPB_10") (pintype "bidirectional"))
    )
    (net (code "69") (name "unconnected-(IC4-XO-Pad13)") (class "Default")
      (node (ref "IC4") (pin "13") (pinfunction "XO_13") (pintype "bidirectional"))
    )
  )
)
